# volume_ctrl_v2.net
KiCad netlist of a schematic drawn in EAGLE
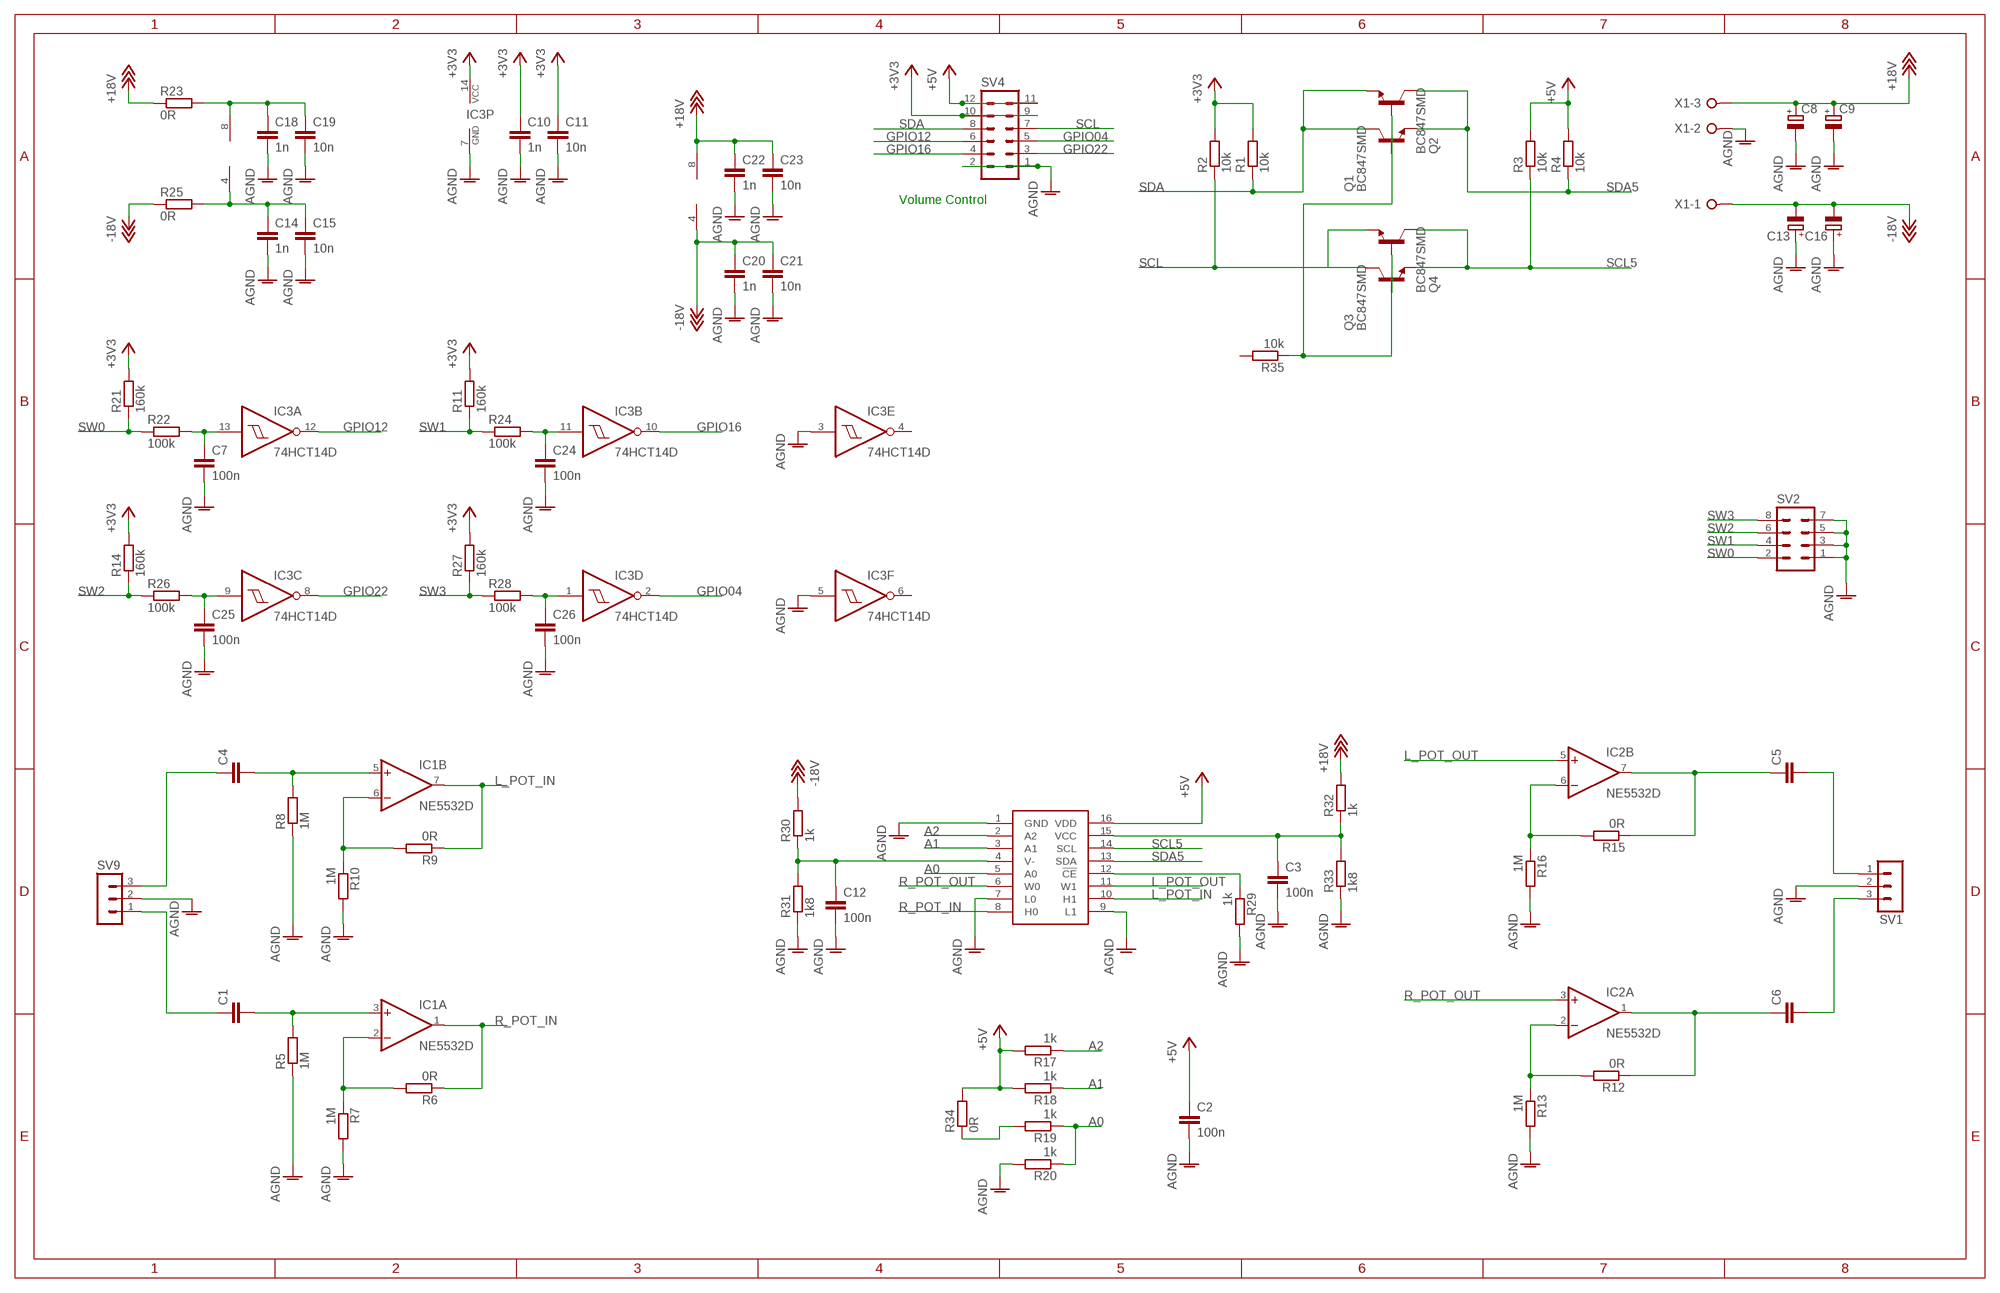
[diagram p0: schematic, sheet 1]

(export (version "E")
  (design (tool "Eeschema 10.0.6"))
  (components
    (comp (ref "C1")
      (value "C22/7")
      (footprint "eagle-import:C22.5B7")
      (libsource (lib "eagle-import") (part "C22/7"))
    )
    (comp (ref "C2")
      (value "100n")
      (footprint "eagle-import:C0603")
      (libsource (lib "eagle-import") (part "C-EUC0603"))
    )
    (comp (ref "C3")
      (value "100n")
      (footprint "eagle-import:C0603")
      (libsource (lib "eagle-import") (part "C-EUC0603"))
    )
    (comp (ref "C4")
      (value "C22/7")
      (footprint "eagle-import:C22.5B7")
      (libsource (lib "eagle-import") (part "C22/7"))
    )
    (comp (ref "C5")
      (value "C22/7")
      (footprint "eagle-import:C22.5B7")
      (libsource (lib "eagle-import") (part "C22/7"))
    )
    (comp (ref "C6")
      (value "C22/7")
      (footprint "eagle-import:C22.5B7")
      (libsource (lib "eagle-import") (part "C22/7"))
    )
    (comp (ref "C7")
      (value "100n")
      (footprint "eagle-import:C0603")
      (libsource (lib "eagle-import") (part "C-EUC0603"))
    )
    (comp (ref "C8")
      (value "CPOL-EUE5-10.5")
      (footprint "eagle-import:E5-10,5")
      (libsource (lib "eagle-import") (part "CPOL-EUE5-10.5"))
    )
    (comp (ref "C9")
      (value "CPOL-EUE5-10.5")
      (footprint "eagle-import:E5-10,5")
      (libsource (lib "eagle-import") (part "CPOL-EUE5-10.5"))
    )
    (comp (ref "C10")
      (value "1n")
      (footprint "eagle-import:C0603")
      (libsource (lib "eagle-import") (part "C-EUC0603"))
    )
    (comp (ref "C11")
      (value "10n")
      (footprint "eagle-import:C0603")
      (libsource (lib "eagle-import") (part "C-EUC0603"))
    )
    (comp (ref "C12")
      (value "100n")
      (footprint "eagle-import:C0603")
      (libsource (lib "eagle-import") (part "C-EUC0603"))
    )
    (comp (ref "C13")
      (value "CPOL-EUE5-10.5")
      (footprint "eagle-import:E5-10,5")
      (libsource (lib "eagle-import") (part "CPOL-EUE5-10.5"))
    )
    (comp (ref "C14")
      (value "1n")
      (footprint "eagle-import:C0603")
      (libsource (lib "eagle-import") (part "C-EUC0603"))
    )
    (comp (ref "C15")
      (value "10n")
      (footprint "eagle-import:C0603")
      (libsource (lib "eagle-import") (part "C-EUC0603"))
    )
    (comp (ref "C16")
      (value "CPOL-EUE5-10.5")
      (footprint "eagle-import:E5-10,5")
      (libsource (lib "eagle-import") (part "CPOL-EUE5-10.5"))
    )
    (comp (ref "C18")
      (value "1n")
      (footprint "eagle-import:C0603")
      (libsource (lib "eagle-import") (part "C-EUC0603"))
    )
    (comp (ref "C19")
      (value "10n")
      (footprint "eagle-import:C0603")
      (libsource (lib "eagle-import") (part "C-EUC0603"))
    )
    (comp (ref "C20")
      (value "1n")
      (footprint "eagle-import:C0603")
      (libsource (lib "eagle-import") (part "C-EUC0603"))
    )
    (comp (ref "C21")
      (value "10n")
      (footprint "eagle-import:C0603")
      (libsource (lib "eagle-import") (part "C-EUC0603"))
    )
    (comp (ref "C22")
      (value "1n")
      (footprint "eagle-import:C0603")
      (libsource (lib "eagle-import") (part "C-EUC0603"))
    )
    (comp (ref "C23")
      (value "10n")
      (footprint "eagle-import:C0603")
      (libsource (lib "eagle-import") (part "C-EUC0603"))
    )
    (comp (ref "C24")
      (value "100n")
      (footprint "eagle-import:C0603")
      (libsource (lib "eagle-import") (part "C-EUC0603"))
    )
    (comp (ref "C25")
      (value "100n")
      (footprint "eagle-import:C0603")
      (libsource (lib "eagle-import") (part "C-EUC0603"))
    )
    (comp (ref "C26")
      (value "100n")
      (footprint "eagle-import:C0603")
      (libsource (lib "eagle-import") (part "C-EUC0603"))
    )
    (comp (ref "IC1")
      (value "NE5532D")
      (footprint "eagle-import:SO08")
      (libsource (lib "eagle-import") (part "NE5532D"))
    )
    (comp (ref "IC2")
      (value "NE5532D")
      (footprint "eagle-import:SO08")
      (libsource (lib "eagle-import") (part "NE5532D"))
    )
    (comp (ref "IC3")
      (value "74HCT14D")
      (footprint "eagle-import:SO14")
      (libsource (lib "eagle-import") (part "7414DHCT"))
    )
    (comp (ref "IC4")
      (value "DS1882")
      (footprint "eagle-import:SO16")
      (libsource (lib "eagle-import") (part "DS1882"))
    )
    (comp (ref "Q1")
      (value "BC847SMD")
      (footprint "eagle-import:SOT23")
      (libsource (lib "eagle-import") (part "BC847SMD"))
    )
    (comp (ref "Q2")
      (value "BC847SMD")
      (footprint "eagle-import:SOT23")
      (libsource (lib "eagle-import") (part "BC847SMD"))
    )
    (comp (ref "Q3")
      (value "BC847SMD")
      (footprint "eagle-import:SOT23")
      (libsource (lib "eagle-import") (part "BC847SMD"))
    )
    (comp (ref "Q4")
      (value "BC847SMD")
      (footprint "eagle-import:SOT23")
      (libsource (lib "eagle-import") (part "BC847SMD"))
    )
    (comp (ref "R1")
      (value "10k")
      (footprint "eagle-import:R0805")
      (libsource (lib "eagle-import") (part "resistor_R-EU_R0805"))
    )
    (comp (ref "R2")
      (value "10k")
      (footprint "eagle-import:R0805")
      (libsource (lib "eagle-import") (part "resistor_R-EU_R0805"))
    )
    (comp (ref "R3")
      (value "10k")
      (footprint "eagle-import:R0805")
      (libsource (lib "eagle-import") (part "resistor_R-EU_R0805"))
    )
    (comp (ref "R4")
      (value "10k")
      (footprint "eagle-import:R1206")
      (libsource (lib "eagle-import") (part "R-EU_R1206"))
    )
    (comp (ref "R5")
      (value "1M")
      (footprint "eagle-import:R0805")
      (libsource (lib "eagle-import") (part "resistor_R-EU_R0805"))
    )
    (comp (ref "R6")
      (value "0R")
      (footprint "eagle-import:R0805")
      (libsource (lib "eagle-import") (part "resistor_R-EU_R0805"))
    )
    (comp (ref "R7")
      (value "1M")
      (footprint "eagle-import:R0805")
      (libsource (lib "eagle-import") (part "resistor_R-EU_R0805"))
    )
    (comp (ref "R8")
      (value "1M")
      (footprint "eagle-import:R0805")
      (libsource (lib "eagle-import") (part "resistor_R-EU_R0805"))
    )
    (comp (ref "R9")
      (value "0R")
      (footprint "eagle-import:R0805")
      (libsource (lib "eagle-import") (part "resistor_R-EU_R0805"))
    )
    (comp (ref "R10")
      (value "1M")
      (footprint "eagle-import:R0805")
      (libsource (lib "eagle-import") (part "resistor_R-EU_R0805"))
    )
    (comp (ref "R11")
      (value "160k")
      (footprint "eagle-import:R1206")
      (libsource (lib "eagle-import") (part "R-EU_R1206"))
    )
    (comp (ref "R12")
      (value "0R")
      (footprint "eagle-import:R0805")
      (libsource (lib "eagle-import") (part "resistor_R-EU_R0805"))
    )
    (comp (ref "R13")
      (value "1M")
      (footprint "eagle-import:R0805")
      (libsource (lib "eagle-import") (part "resistor_R-EU_R0805"))
    )
    (comp (ref "R14")
      (value "160k")
      (footprint "eagle-import:R1206")
      (libsource (lib "eagle-import") (part "R-EU_R1206"))
    )
    (comp (ref "R15")
      (value "0R")
      (footprint "eagle-import:R0805")
      (libsource (lib "eagle-import") (part "resistor_R-EU_R0805"))
    )
    (comp (ref "R16")
      (value "1M")
      (footprint "eagle-import:R0805")
      (libsource (lib "eagle-import") (part "resistor_R-EU_R0805"))
    )
    (comp (ref "R17")
      (value "1k")
      (footprint "eagle-import:R0805")
      (libsource (lib "eagle-import") (part "resistor_R-EU_R0805"))
    )
    (comp (ref "R18")
      (value "1k")
      (footprint "eagle-import:R0805")
      (libsource (lib "eagle-import") (part "resistor_R-EU_R0805"))
    )
    (comp (ref "R19")
      (value "1k")
      (footprint "eagle-import:R0805")
      (libsource (lib "eagle-import") (part "resistor_R-EU_R0805"))
    )
    (comp (ref "R20")
      (value "1k")
      (footprint "eagle-import:R0805")
      (libsource (lib "eagle-import") (part "resistor_R-EU_R0805"))
    )
    (comp (ref "R21")
      (value "160k")
      (footprint "eagle-import:R0603")
      (libsource (lib "eagle-import") (part "R-EU_R0603"))
    )
    (comp (ref "R22")
      (value "100k")
      (footprint "eagle-import:R0603")
      (libsource (lib "eagle-import") (part "R-EU_R0603"))
    )
    (comp (ref "R23")
      (value "0R")
      (footprint "eagle-import:R1206")
      (libsource (lib "eagle-import") (part "R-EU_R1206"))
    )
    (comp (ref "R24")
      (value "100k")
      (footprint "eagle-import:R0603")
      (libsource (lib "eagle-import") (part "R-EU_R0603"))
    )
    (comp (ref "R25")
      (value "0R")
      (footprint "eagle-import:R1206")
      (libsource (lib "eagle-import") (part "R-EU_R1206"))
    )
    (comp (ref "R26")
      (value "100k")
      (footprint "eagle-import:R0603")
      (libsource (lib "eagle-import") (part "R-EU_R0603"))
    )
    (comp (ref "R27")
      (value "160k")
      (footprint "eagle-import:R0603")
      (libsource (lib "eagle-import") (part "R-EU_R0603"))
    )
    (comp (ref "R28")
      (value "100k")
      (footprint "eagle-import:R0603")
      (libsource (lib "eagle-import") (part "R-EU_R0603"))
    )
    (comp (ref "R29")
      (value "1k")
      (footprint "eagle-import:R0805")
      (libsource (lib "eagle-import") (part "resistor_R-EU_R0805"))
    )
    (comp (ref "R30")
      (value "1k")
      (footprint "eagle-import:R0805")
      (libsource (lib "eagle-import") (part "resistor_R-EU_R0805"))
    )
    (comp (ref "R31")
      (value "1k8")
      (footprint "eagle-import:R0805")
      (libsource (lib "eagle-import") (part "resistor_R-EU_R0805"))
    )
    (comp (ref "R32")
      (value "1k")
      (footprint "eagle-import:R0805")
      (libsource (lib "eagle-import") (part "resistor_R-EU_R0805"))
    )
    (comp (ref "R33")
      (value "1k8")
      (footprint "eagle-import:R0805")
      (libsource (lib "eagle-import") (part "resistor_R-EU_R0805"))
    )
    (comp (ref "R34")
      (value "0R")
      (footprint "eagle-import:R1206")
      (libsource (lib "eagle-import") (part "R-EU_R1206"))
    )
    (comp (ref "R35")
      (value "10k")
      (footprint "eagle-import:R0805")
      (libsource (lib "eagle-import") (part "resistor_R-EU_R0805"))
    )
    (comp (ref "SV1")
      (value "MA03-1")
      (footprint "eagle-import:MA03-1")
      (libsource (lib "eagle-import") (part "MA03-1"))
    )
    (comp (ref "SV2")
      (value "MA04-2")
      (footprint "eagle-import:MA04-2")
      (libsource (lib "eagle-import") (part "MA04-2"))
    )
    (comp (ref "SV4")
      (value "MA06-2")
      (footprint "eagle-import:MA06-2")
      (libsource (lib "eagle-import") (part "MA06-2"))
    )
    (comp (ref "SV9")
      (value "MA03-1")
      (footprint "eagle-import:MA03-1")
      (libsource (lib "eagle-import") (part "MA03-1"))
    )
    (comp (ref "X1")
      (value "W237-3E")
      (footprint "eagle-import:W237-3E")
      (libsource (lib "eagle-import") (part "W237-3E"))
    )
  )
  (nets
    (net (code "1") (name "+3V3") (class "Default")
      (node (ref "C10") (pin "1") (pinfunction "1_1") (pintype "passive"))
      (node (ref "C11") (pin "1") (pinfunction "1_1") (pintype "passive"))
      (node (ref "IC3") (pin "14") (pinfunction "VCC_14") (pintype "power_in"))
      (node (ref "R1") (pin "2") (pinfunction "2_2") (pintype "passive"))
      (node (ref "R11") (pin "2") (pinfunction "2_2") (pintype "passive"))
      (node (ref "R14") (pin "2") (pinfunction "2_2") (pintype "passive"))
      (node (ref "R2") (pin "2") (pinfunction "2_2") (pintype "passive"))
      (node (ref "R21") (pin "2") (pinfunction "2_2") (pintype "passive"))
      (node (ref "R27") (pin "2") (pinfunction "2_2") (pintype "passive"))
      (node (ref "SV4") (pin "10") (pinfunction "10_10") (pintype "passive"))
      (node (ref "SV4") (pin "9") (pinfunction "9_9") (pintype "passive"))
    )
    (net (code "2") (name "+5V") (class "Default")
      (node (ref "C2") (pin "1") (pinfunction "1_1") (pintype "passive"))
      (node (ref "IC4") (pin "16") (pinfunction "VDD_16") (pintype "power_in"))
      (node (ref "R17") (pin "2") (pinfunction "2_2") (pintype "passive"))
      (node (ref "R18") (pin "2") (pinfunction "2_2") (pintype "passive"))
      (node (ref "R3") (pin "2") (pinfunction "2_2") (pintype "passive"))
      (node (ref "R34") (pin "2") (pinfunction "2_2") (pintype "passive"))
      (node (ref "R4") (pin "2") (pinfunction "2_2") (pintype "passive"))
      (node (ref "SV4") (pin "11") (pinfunction "11_11") (pintype "passive"))
      (node (ref "SV4") (pin "12") (pinfunction "12_12") (pintype "passive"))
    )
    (net (code "3") (name "+18V") (class "Default")
      (node (ref "C22") (pin "1") (pinfunction "1_1") (pintype "passive"))
      (node (ref "C23") (pin "1") (pinfunction "1_1") (pintype "passive"))
      (node (ref "C8") (pin "+") (pinfunction "+_+") (pintype "passive"))
      (node (ref "C9") (pin "+") (pinfunction "+_+") (pintype "passive"))
      (node (ref "IC2") (pin "8") (pinfunction "V+_8") (pintype "power_in"))
      (node (ref "R23") (pin "1") (pinfunction "1_1") (pintype "passive"))
      (node (ref "R32") (pin "2") (pinfunction "2_2") (pintype "passive"))
      (node (ref "X1") (pin "3") (pinfunction "KL_3") (pintype "passive"))
    )
    (net (code "4") (name "-18V") (class "Default")
      (node (ref "C13") (pin "-") (pinfunction "-_-") (pintype "passive"))
      (node (ref "C16") (pin "-") (pinfunction "-_-") (pintype "passive"))
      (node (ref "C20") (pin "1") (pinfunction "1_1") (pintype "passive"))
      (node (ref "C21") (pin "1") (pinfunction "1_1") (pintype "passive"))
      (node (ref "IC2") (pin "4") (pinfunction "V-_4") (pintype "power_in"))
      (node (ref "R25") (pin "1") (pinfunction "1_1") (pintype "passive"))
      (node (ref "R30") (pin "2") (pinfunction "2_2") (pintype "passive"))
      (node (ref "X1") (pin "1") (pinfunction "KL_1") (pintype "passive"))
    )
    (net (code "5") (name "/A0") (class "Default")
      (node (ref "IC4") (pin "5") (pinfunction "A0_5") (pintype "bidirectional"))
      (node (ref "R19") (pin "1") (pinfunction "1_1") (pintype "passive"))
      (node (ref "R20") (pin "1") (pinfunction "1_1") (pintype "passive"))
    )
    (net (code "6") (name "/A1") (class "Default")
      (node (ref "IC4") (pin "3") (pinfunction "A1_3") (pintype "bidirectional"))
      (node (ref "R18") (pin "1") (pinfunction "1_1") (pintype "passive"))
    )
    (net (code "7") (name "/A2") (class "Default")
      (node (ref "IC4") (pin "2") (pinfunction "A2_2") (pintype "bidirectional"))
      (node (ref "R17") (pin "1") (pinfunction "1_1") (pintype "passive"))
    )
    (net (code "8") (name "/GPIO04") (class "Default")
      (node (ref "IC3") (pin "2") (pinfunction "O_2") (pintype "output"))
      (node (ref "SV4") (pin "5") (pinfunction "5_5") (pintype "passive"))
    )
    (net (code "9") (name "/GPIO12") (class "Default")
      (node (ref "IC3") (pin "12") (pinfunction "O_12") (pintype "output"))
      (node (ref "SV4") (pin "6") (pinfunction "6_6") (pintype "passive"))
    )
    (net (code "10") (name "/GPIO16") (class "Default")
      (node (ref "IC3") (pin "10") (pinfunction "O_10") (pintype "output"))
      (node (ref "SV4") (pin "4") (pinfunction "4_4") (pintype "passive"))
    )
    (net (code "11") (name "/GPIO22") (class "Default")
      (node (ref "IC3") (pin "8") (pinfunction "O_8") (pintype "output"))
      (node (ref "SV4") (pin "3") (pinfunction "3_3") (pintype "passive"))
    )
    (net (code "12") (name "/L_POT_IN") (class "Default")
      (node (ref "IC1") (pin "7") (pinfunction "OUT_7") (pintype "output"))
      (node (ref "IC4") (pin "10") (pinfunction "H1_10") (pintype "bidirectional"))
      (node (ref "R9") (pin "1") (pinfunction "1_1") (pintype "passive"))
    )
    (net (code "13") (name "/L_POT_OUT") (class "Default")
      (node (ref "IC2") (pin "5") (pinfunction "+IN_5") (pintype "input"))
      (node (ref "IC4") (pin "11") (pinfunction "W1_11") (pintype "bidirectional"))
    )
    (net (code "14") (name "/R_POT_IN") (class "Default")
      (node (ref "IC1") (pin "1") (pinfunction "OUT_1") (pintype "output"))
      (node (ref "IC4") (pin "8") (pinfunction "H0_8") (pintype "bidirectional"))
      (node (ref "R6") (pin "1") (pinfunction "1_1") (pintype "passive"))
    )
    (net (code "15") (name "/R_POT_OUT") (class "Default")
      (node (ref "IC2") (pin "3") (pinfunction "+IN_3") (pintype "input"))
      (node (ref "IC4") (pin "6") (pinfunction "W0_6") (pintype "bidirectional"))
    )
    (net (code "16") (name "/SCL") (class "Default")
      (node (ref "Q3") (pin "3") (pinfunction "C_3") (pintype "passive"))
      (node (ref "Q4") (pin "2") (pinfunction "E_2") (pintype "passive"))
      (node (ref "R2") (pin "1") (pinfunction "1_1") (pintype "passive"))
      (node (ref "SV4") (pin "7") (pinfunction "7_7") (pintype "passive"))
    )
    (net (code "17") (name "/SCL5") (class "Default")
      (node (ref "IC4") (pin "14") (pinfunction "SCL_14") (pintype "bidirectional"))
      (node (ref "Q3") (pin "2") (pinfunction "E_2") (pintype "passive"))
      (node (ref "Q4") (pin "3") (pinfunction "C_3") (pintype "passive"))
      (node (ref "R3") (pin "1") (pinfunction "1_1") (pintype "passive"))
    )
    (net (code "18") (name "/SDA") (class "Default")
      (node (ref "Q1") (pin "3") (pinfunction "C_3") (pintype "passive"))
      (node (ref "Q2") (pin "2") (pinfunction "E_2") (pintype "passive"))
      (node (ref "R1") (pin "1") (pinfunction "1_1") (pintype "passive"))
      (node (ref "SV4") (pin "8") (pinfunction "8_8") (pintype "passive"))
    )
    (net (code "19") (name "/SDA5") (class "Default")
      (node (ref "IC4") (pin "13") (pinfunction "SDA_13") (pintype "bidirectional"))
      (node (ref "Q1") (pin "2") (pinfunction "E_2") (pintype "passive"))
      (node (ref "Q2") (pin "3") (pinfunction "C_3") (pintype "passive"))
      (node (ref "R4") (pin "1") (pinfunction "1_1") (pintype "passive"))
    )
    (net (code "20") (name "/SW0") (class "Default")
      (node (ref "R21") (pin "1") (pinfunction "1_1") (pintype "passive"))
      (node (ref "R22") (pin "1") (pinfunction "1_1") (pintype "passive"))
      (node (ref "SV2") (pin "2") (pinfunction "2_2") (pintype "passive"))
    )
    (net (code "21") (name "/SW1") (class "Default")
      (node (ref "R11") (pin "1") (pinfunction "1_1") (pintype "passive"))
      (node (ref "R24") (pin "1") (pinfunction "1_1") (pintype "passive"))
      (node (ref "SV2") (pin "4") (pinfunction "4_4") (pintype "passive"))
    )
    (net (code "22") (name "/SW2") (class "Default")
      (node (ref "R14") (pin "1") (pinfunction "1_1") (pintype "passive"))
      (node (ref "R26") (pin "1") (pinfunction "1_1") (pintype "passive"))
      (node (ref "SV2") (pin "6") (pinfunction "6_6") (pintype "passive"))
    )
    (net (code "23") (name "/SW3") (class "Default")
      (node (ref "R27") (pin "1") (pinfunction "1_1") (pintype "passive"))
      (node (ref "R28") (pin "1") (pinfunction "1_1") (pintype "passive"))
      (node (ref "SV2") (pin "8") (pinfunction "8_8") (pintype "passive"))
    )
    (net (code "24") (name "AGND") (class "Default")
      (node (ref "C10") (pin "2") (pinfunction "2_2") (pintype "passive"))
      (node (ref "C11") (pin "2") (pinfunction "2_2") (pintype "passive"))
      (node (ref "C12") (pin "2") (pinfunction "2_2") (pintype "passive"))
      (node (ref "C13") (pin "+") (pinfunction "+_+") (pintype "passive"))
      (node (ref "C14") (pin "2") (pinfunction "2_2") (pintype "passive"))
      (node (ref "C15") (pin "2") (pinfunction "2_2") (pintype "passive"))
      (node (ref "C16") (pin "+") (pinfunction "+_+") (pintype "passive"))
      (node (ref "C18") (pin "2") (pinfunction "2_2") (pintype "passive"))
      (node (ref "C19") (pin "2") (pinfunction "2_2") (pintype "passive"))
      (node (ref "C2") (pin "2") (pinfunction "2_2") (pintype "passive"))
      (node (ref "C20") (pin "2") (pinfunction "2_2") (pintype "passive"))
      (node (ref "C21") (pin "2") (pinfunction "2_2") (pintype "passive"))
      (node (ref "C22") (pin "2") (pinfunction "2_2") (pintype "passive"))
      (node (ref "C23") (pin "2") (pinfunction "2_2") (pintype "passive"))
      (node (ref "C24") (pin "2") (pinfunction "2_2") (pintype "passive"))
      (node (ref "C25") (pin "2") (pinfunction "2_2") (pintype "passive"))
      (node (ref "C26") (pin "2") (pinfunction "2_2") (pintype "passive"))
      (node (ref "C3") (pin "2") (pinfunction "2_2") (pintype "passive"))
      (node (ref "C7") (pin "2") (pinfunction "2_2") (pintype "passive"))
      (node (ref "C8") (pin "-") (pinfunction "-_-") (pintype "passive"))
      (node (ref "C9") (pin "-") (pinfunction "-_-") (pintype "passive"))
      (node (ref "IC3") (pin "3") (pinfunction "I_3") (pintype "input"))
      (node (ref "IC3") (pin "5") (pinfunction "I_5") (pintype "input"))
      (node (ref "IC3") (pin "7") (pinfunction "GND_7") (pintype "power_in"))
      (node (ref "IC4") (pin "1") (pinfunction "GND_1") (pintype "power_in"))
      (node (ref "IC4") (pin "7") (pinfunction "L0_7") (pintype "bidirectional"))
      (node (ref "IC4") (pin "9") (pinfunction "L1_9") (pintype "bidirectional"))
      (node (ref "R10") (pin "2") (pinfunction "2_2") (pintype "passive"))
      (node (ref "R13") (pin "2") (pinfunction "2_2") (pintype "passive"))
      (node (ref "R16") (pin "2") (pinfunction "2_2") (pintype "passive"))
      (node (ref "R20") (pin "2") (pinfunction "2_2") (pintype "passive"))
      (node (ref "R29") (pin "2") (pinfunction "2_2") (pintype "passive"))
      (node (ref "R31") (pin "1") (pinfunction "1_1") (pintype "passive"))
      (node (ref "R33") (pin "1") (pinfunction "1_1") (pintype "passive"))
      (node (ref "R5") (pin "1") (pinfunction "1_1") (pintype "passive"))
      (node (ref "R7") (pin "2") (pinfunction "2_2") (pintype "passive"))
      (node (ref "R8") (pin "1") (pinfunction "1_1") (pintype "passive"))
      (node (ref "SV1") (pin "2") (pinfunction "2_2") (pintype "passive"))
      (node (ref "SV2") (pin "1") (pinfunction "1_1") (pintype "passive"))
      (node (ref "SV2") (pin "3") (pinfunction "3_3") (pintype "passive"))
      (node (ref "SV2") (pin "5") (pinfunction "5_5") (pintype "passive"))
      (node (ref "SV2") (pin "7") (pinfunction "7_7") (pintype "passive"))
      (node (ref "SV4") (pin "1") (pinfunction "1_1") (pintype "passive"))
      (node (ref "SV4") (pin "2") (pinfunction "2_2") (pintype "passive"))
      (node (ref "SV9") (pin "2") (pinfunction "2_2") (pintype "passive"))
      (node (ref "X1") (pin "2") (pinfunction "KL_2") (pintype "passive"))
    )
    (net (code "25") (name "Net-(C1-Pad1)") (class "Default")
      (node (ref "C1") (pin "1") (pinfunction "1_1") (pintype "passive"))
      (node (ref "SV9") (pin "1") (pinfunction "1_1") (pintype "passive"))
    )
    (net (code "26") (name "Net-(C4-Pad1)") (class "Default")
      (node (ref "C4") (pin "1") (pinfunction "1_1") (pintype "passive"))
      (node (ref "SV9") (pin "3") (pinfunction "3_3") (pintype "passive"))
    )
    (net (code "27") (name "Net-(C5-Pad2)") (class "Default")
      (node (ref "C5") (pin "2") (pinfunction "2_2") (pintype "passive"))
      (node (ref "SV1") (pin "1") (pinfunction "1_1") (pintype "passive"))
    )
    (net (code "28") (name "Net-(C6-Pad2)") (class "Default")
      (node (ref "C6") (pin "2") (pinfunction "2_2") (pintype "passive"))
      (node (ref "SV1") (pin "3") (pinfunction "3_3") (pintype "passive"))
    )
    (net (code "29") (name "Net-(IC1A-+IN)") (class "Default")
      (node (ref "C1") (pin "2") (pinfunction "2_2") (pintype "passive"))
      (node (ref "IC1") (pin "3") (pinfunction "+IN_3") (pintype "input"))
      (node (ref "R5") (pin "2") (pinfunction "2_2") (pintype "passive"))
    )
    (net (code "30") (name "Net-(IC1A--IN)") (class "Default")
      (node (ref "IC1") (pin "2") (pinfunction "-IN_2") (pintype "input"))
      (node (ref "R6") (pin "2") (pinfunction "2_2") (pintype "passive"))
      (node (ref "R7") (pin "1") (pinfunction "1_1") (pintype "passive"))
    )
    (net (code "31") (name "Net-(IC1B-+IN)") (class "Default")
      (node (ref "C4") (pin "2") (pinfunction "2_2") (pintype "passive"))
      (node (ref "IC1") (pin "5") (pinfunction "+IN_5") (pintype "input"))
      (node (ref "R8") (pin "2") (pinfunction "2_2") (pintype "passive"))
    )
    (net (code "32") (name "Net-(IC1B--IN)") (class "Default")
      (node (ref "IC1") (pin "6") (pinfunction "-IN_6") (pintype "input"))
      (node (ref "R10") (pin "1") (pinfunction "1_1") (pintype "passive"))
      (node (ref "R9") (pin "2") (pinfunction "2_2") (pintype "passive"))
    )
    (net (code "33") (name "Net-(IC1C-V+)") (class "Default")
      (node (ref "C18") (pin "1") (pinfunction "1_1") (pintype "passive"))
      (node (ref "C19") (pin "1") (pinfunction "1_1") (pintype "passive"))
      (node (ref "IC1") (pin "8") (pinfunction "V+_8") (pintype "power_in"))
      (node (ref "R23") (pin "2") (pinfunction "2_2") (pintype "passive"))
    )
    (net (code "34") (name "Net-(IC1C-V-)") (class "Default")
      (node (ref "C14") (pin "1") (pinfunction "1_1") (pintype "passive"))
      (node (ref "C15") (pin "1") (pinfunction "1_1") (pintype "passive"))
      (node (ref "IC1") (pin "4") (pinfunction "V-_4") (pintype "power_in"))
      (node (ref "R25") (pin "2") (pinfunction "2_2") (pintype "passive"))
    )
    (net (code "35") (name "Net-(IC2A--IN)") (class "Default")
      (node (ref "IC2") (pin "2") (pinfunction "-IN_2") (pintype "input"))
      (node (ref "R12") (pin "2") (pinfunction "2_2") (pintype "passive"))
      (node (ref "R13") (pin "1") (pinfunction "1_1") (pintype "passive"))
    )
    (net (code "36") (name "Net-(IC2A-OUT)") (class "Default")
      (node (ref "C6") (pin "1") (pinfunction "1_1") (pintype "passive"))
      (node (ref "IC2") (pin "1") (pinfunction "OUT_1") (pintype "output"))
      (node (ref "R12") (pin "1") (pinfunction "1_1") (pintype "passive"))
    )
    (net (code "37") (name "Net-(IC2B--IN)") (class "Default")
      (node (ref "IC2") (pin "6") (pinfunction "-IN_6") (pintype "input"))
      (node (ref "R15") (pin "2") (pinfunction "2_2") (pintype "passive"))
      (node (ref "R16") (pin "1") (pinfunction "1_1") (pintype "passive"))
    )
    (net (code "38") (name "Net-(IC2B-OUT)") (class "Default")
      (node (ref "C5") (pin "1") (pinfunction "1_1") (pintype "passive"))
      (node (ref "IC2") (pin "7") (pinfunction "OUT_7") (pintype "output"))
      (node (ref "R15") (pin "1") (pinfunction "1_1") (pintype "passive"))
    )
    (net (code "39") (name "Net-(IC3A-I)") (class "Default")
      (node (ref "C7") (pin "1") (pinfunction "1_1") (pintype "passive"))
      (node (ref "IC3") (pin "13") (pinfunction "I_13") (pintype "input"))
      (node (ref "R22") (pin "2") (pinfunction "2_2") (pintype "passive"))
    )
    (net (code "40") (name "Net-(IC3B-I)") (class "Default")
      (node (ref "C24") (pin "1") (pinfunction "1_1") (pintype "passive"))
      (node (ref "IC3") (pin "11") (pinfunction "I_11") (pintype "input"))
      (node (ref "R24") (pin "2") (pinfunction "2_2") (pintype "passive"))
    )
    (net (code "41") (name "Net-(IC3C-I)") (class "Default")
      (node (ref "C25") (pin "1") (pinfunction "1_1") (pintype "passive"))
      (node (ref "IC3") (pin "9") (pinfunction "I_9") (pintype "input"))
      (node (ref "R26") (pin "2") (pinfunction "2_2") (pintype "passive"))
    )
    (net (code "42") (name "Net-(IC3D-I)") (class "Default")
      (node (ref "C26") (pin "1") (pinfunction "1_1") (pintype "passive"))
      (node (ref "IC3") (pin "1") (pinfunction "I_1") (pintype "input"))
      (node (ref "R28") (pin "2") (pinfunction "2_2") (pintype "passive"))
    )
    (net (code "43") (name "Net-(IC4-V-)") (class "Default")
      (node (ref "C12") (pin "1") (pinfunction "1_1") (pintype "passive"))
      (node (ref "IC4") (pin "4") (pinfunction "V-_4") (pintype "power_in"))
      (node (ref "R30") (pin "1") (pinfunction "1_1") (pintype "passive"))
      (node (ref "R31") (pin "2") (pinfunction "2_2") (pintype "passive"))
    )
    (net (code "44") (name "Net-(IC4-VCC)") (class "Default")
      (node (ref "C3") (pin "1") (pinfunction "1_1") (pintype "passive"))
      (node (ref "IC4") (pin "15") (pinfunction "VCC_15") (pintype "power_in"))
      (node (ref "R32") (pin "1") (pinfunction "1_1") (pintype "passive"))
      (node (ref "R33") (pin "2") (pinfunction "2_2") (pintype "passive"))
    )
    (net (code "45") (name "Net-(IC4-~{CE})") (class "Default")
      (node (ref "IC4") (pin "12") (pinfunction "~{CE}_12") (pintype "bidirectional"))
      (node (ref "R29") (pin "1") (pinfunction "1_1") (pintype "passive"))
    )
    (net (code "46") (name "Net-(Q1-B)") (class "Default")
      (node (ref "Q1") (pin "1") (pinfunction "B_1") (pintype "passive"))
      (node (ref "Q2") (pin "1") (pinfunction "B_1") (pintype "passive"))
      (node (ref "Q3") (pin "1") (pinfunction "B_1") (pintype "passive"))
      (node (ref "Q4") (pin "1") (pinfunction "B_1") (pintype "passive"))
      (node (ref "R35") (pin "1") (pinfunction "1_1") (pintype "passive"))
    )
    (net (code "47") (name "Net-(R19-Pad2)") (class "Default")
      (node (ref "R19") (pin "2") (pinfunction "2_2") (pintype "passive"))
      (node (ref "R34") (pin "1") (pinfunction "1_1") (pintype "passive"))
    )
    (net (code "48") (name "unconnected-(IC3E-O-Pad4)") (class "Default")
      (node (ref "IC3") (pin "4") (pinfunction "O_4") (pintype "output"))
    )
    (net (code "49") (name "unconnected-(IC3F-O-Pad6)") (class "Default")
      (node (ref "IC3") (pin "6") (pinfunction "O_6") (pintype "output"))
    )
    (net (code "50") (name "unconnected-(R35-Pad2)") (class "Default")
      (node (ref "R35") (pin "2") (pinfunction "2_2") (pintype "passive"))
    )
  )
)
